# SAMV71_Xplained_Ultra_EDBG.net
KiCad netlist of a schematic drawn in Altium Designer
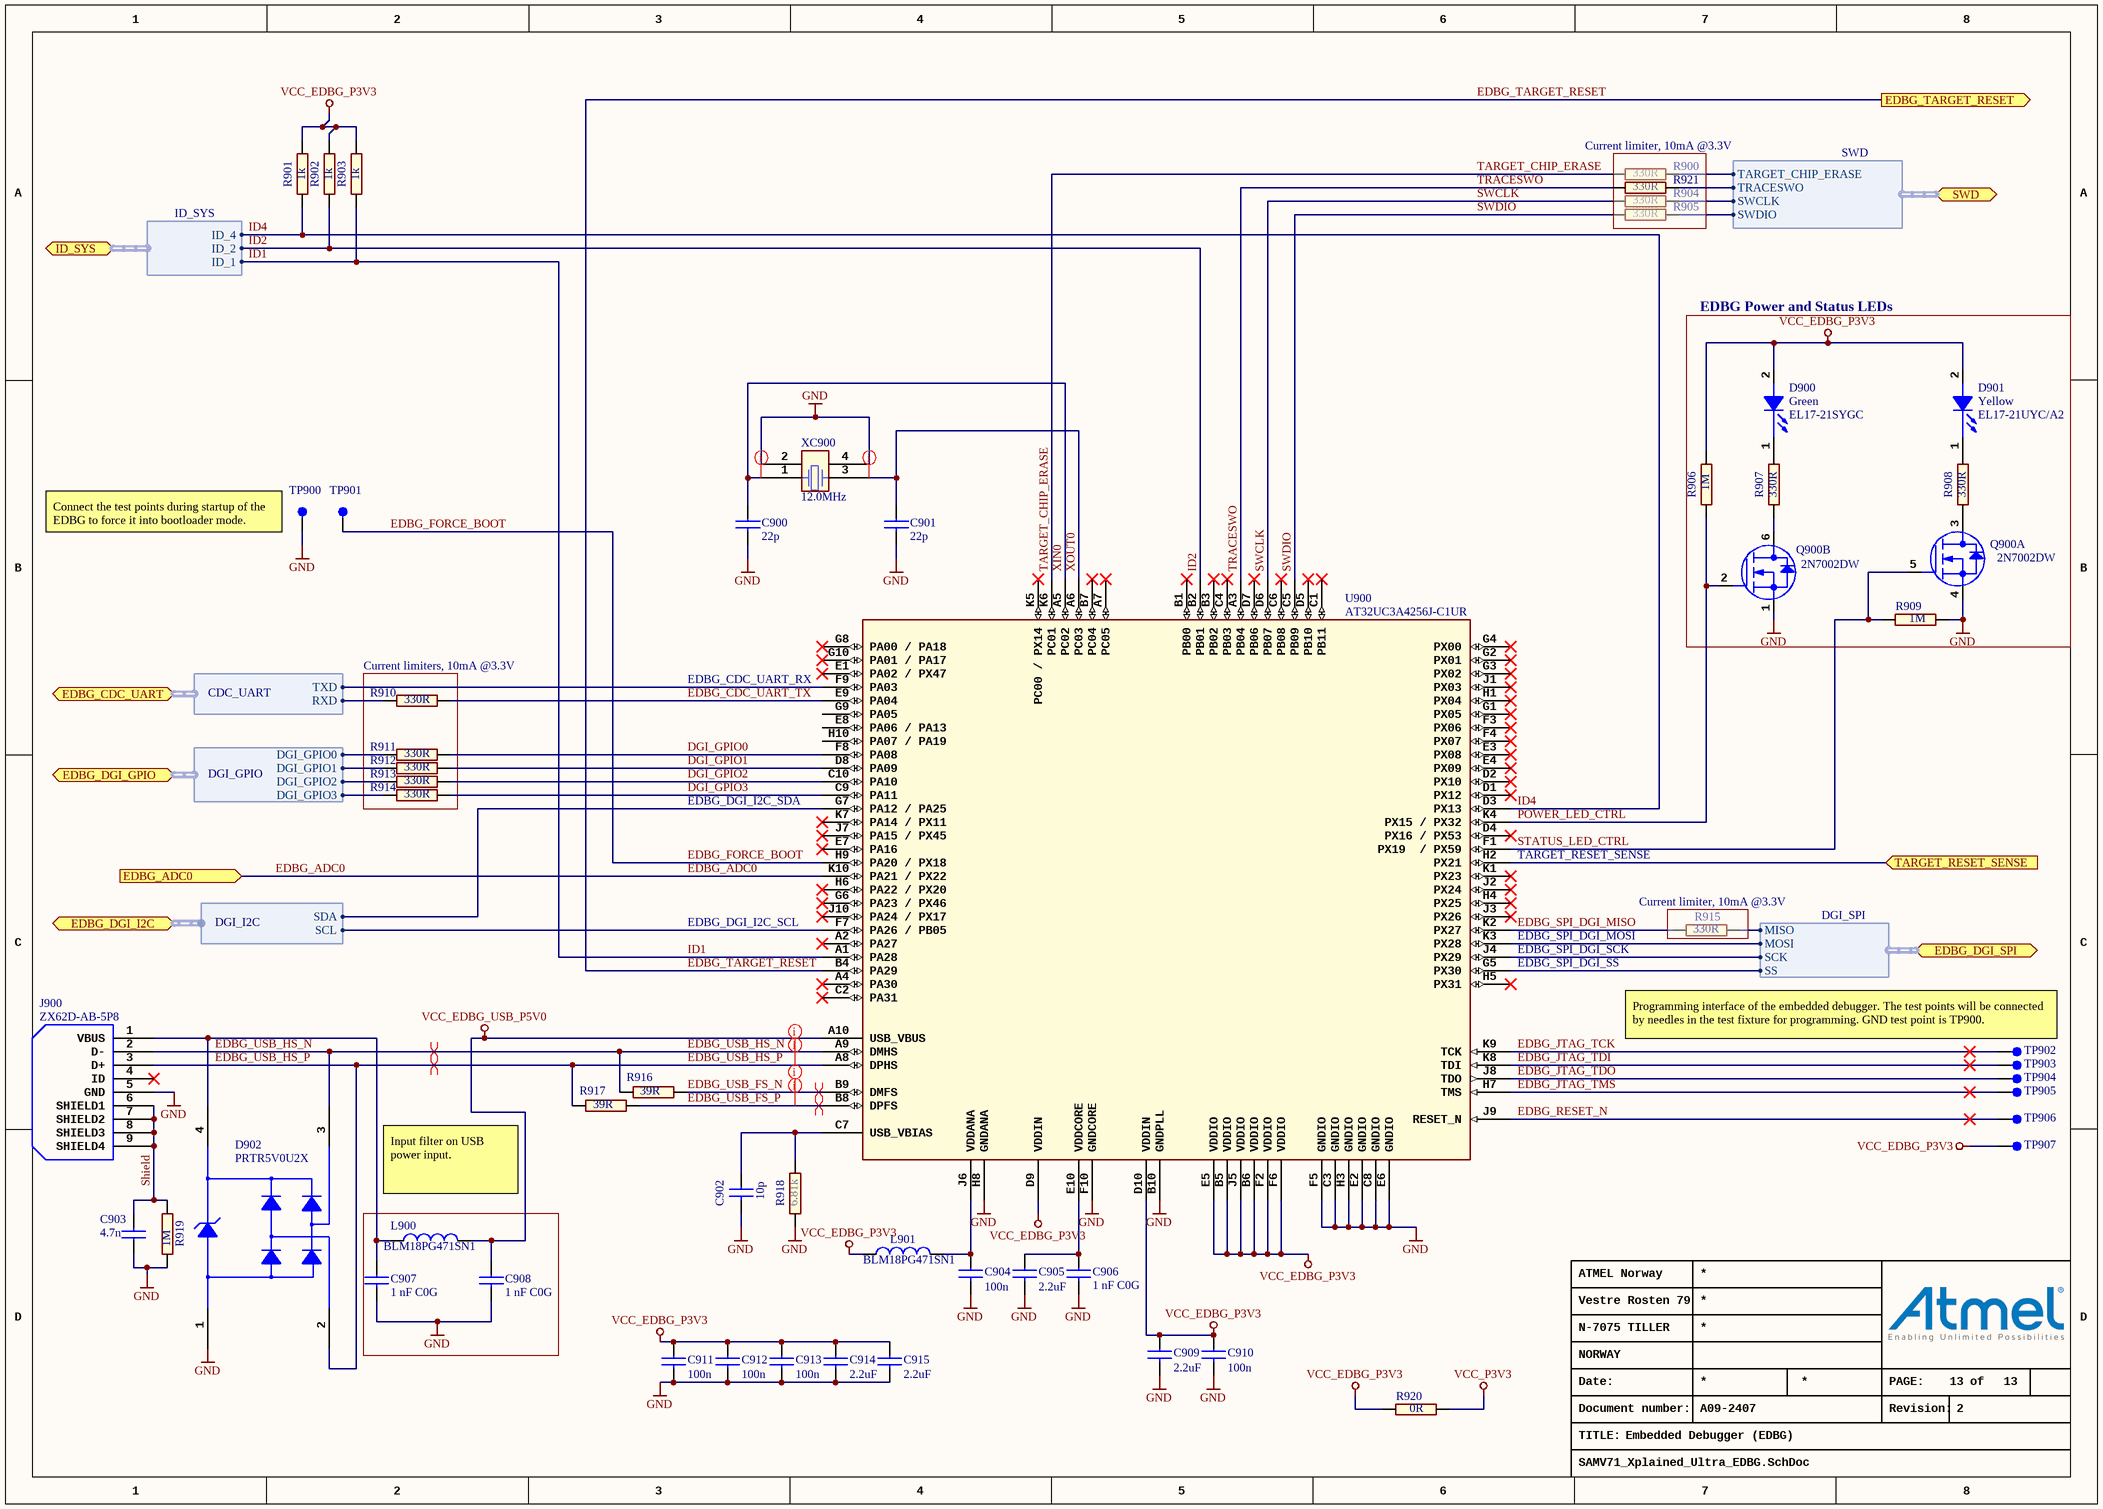
[diagram p0: SAMV71_Xplained_Ultra_EDBG.SchDoc]

(export (version "E")
  (design (tool "Eeschema 10.0.6"))
  (components
    (comp (ref "C900")
      (value "22p")
      (footprint "AP1-00053")
      (description "Ceramic capacitor, SMD 0402, NP0, 50V, +/-5%")
      (fields (field (name "TOLERANCE") "50V, +/-5%"))
      (libsource (lib "AltiumDbLib") (part "CAP-NONPOL"))
    )
    (comp (ref "C901")
      (value "22p")
      (footprint "AP1-00053")
      (description "Ceramic capacitor, SMD 0402, NP0, 50V, +/-5%")
      (fields (field (name "TOLERANCE") "50V, +/-5%"))
      (libsource (lib "AltiumDbLib") (part "CAP-NONPOL"))
    )
    (comp (ref "C902")
      (value "10p")
      (footprint "AP1-00053")
      (description "Ceramic capacitor, SMD 0402, NP0, 50V, +/-5%")
      (fields (field (name "TOLERANCE") "50V, +/-5%"))
      (libsource (lib "AltiumDbLib") (part "CAP-NONPOL"))
    )
    (comp (ref "C903")
      (value "4.7n")
      (footprint "AP1-00053")
      (description "Ceramic capacitor, SMD 0402, X7R, 25V, +/-10%")
      (fields (field (name "TOLERANCE") "25V, +/-10%") (field (name "Comment") "CAP-NONPOL"))
      (libsource (lib "AltiumDbLib") (part "CAP-NONPOL"))
    )
    (comp (ref "C904")
      (value "100n")
      (footprint "AP1-00053")
      (description "Ceramic capacitor, SMD 0402, X7R, 16V, +/-10%")
      (fields (field (name "TOLERANCE") "16V, +/-10%") (field (name "MANUFACTURER") "Kemet"))
      (libsource (lib "AltiumDbLib") (part "CAP-NONPOL"))
    )
    (comp (ref "C905")
      (value "2.2uF")
      (footprint "AP1-00053")
      (description "Ceramic capacitor, SMD 0402, X5R, 6.3V, +/-20%")
      (fields (field (name "TOLERANCE") "±20%") (field (name "MANUFACTURER") "Kemet"))
      (libsource (lib "AltiumDbLib") (part "CAP-NONPOL"))
    )
    (comp (ref "C906")
      (value "1 nF C0G")
      (footprint "AP1-00053")
      (description "Ceramic capacitor, SMD 0402, C0G, 50V, +/-5%")
      (fields (field (name "TOLERANCE") "5%") (field (name "MANUFACTURER") "Murata"))
      (libsource (lib "AltiumDbLib") (part "CAP-NONPOL"))
    )
    (comp (ref "C907")
      (value "1 nF C0G")
      (footprint "AP1-00053")
      (description "Ceramic capacitor, SMD 0402, C0G, 50V, +/-5%")
      (fields (field (name "TOLERANCE") "5%") (field (name "MANUFACTURER") "Murata"))
      (libsource (lib "AltiumDbLib") (part "CAP-NONPOL"))
    )
    (comp (ref "C908")
      (value "1 nF C0G")
      (footprint "AP1-00053")
      (description "Ceramic capacitor, SMD 0402, C0G, 50V, +/-5%")
      (fields (field (name "TOLERANCE") "5%") (field (name "MANUFACTURER") "Murata"))
      (libsource (lib "AltiumDbLib") (part "CAP-NONPOL"))
    )
    (comp (ref "C909")
      (value "2.2uF")
      (footprint "AP1-00053")
      (description "Ceramic capacitor, SMD 0402, X5R, 6.3V, +/-20%")
      (fields (field (name "TOLERANCE") "±20%") (field (name "MANUFACTURER") "Kemet"))
      (libsource (lib "AltiumDbLib") (part "CAP-NONPOL"))
    )
    (comp (ref "C910")
      (value "100n")
      (footprint "AP1-00053")
      (description "Ceramic capacitor, SMD 0402, X7R, 16V, +/-10%")
      (fields (field (name "TOLERANCE") "16V, +/-10%") (field (name "MANUFACTURER") "Kemet"))
      (libsource (lib "AltiumDbLib") (part "CAP-NONPOL"))
    )
    (comp (ref "C911")
      (value "100n")
      (footprint "AP1-00053")
      (description "Ceramic capacitor, SMD 0402, X7R, 16V, +/-10%")
      (fields (field (name "TOLERANCE") "16V, +/-10%") (field (name "MANUFACTURER") "Kemet"))
      (libsource (lib "AltiumDbLib") (part "CAP-NONPOL"))
    )
    (comp (ref "C912")
      (value "100n")
      (footprint "AP1-00053")
      (description "Ceramic capacitor, SMD 0402, X7R, 16V, +/-10%")
      (fields (field (name "TOLERANCE") "16V, +/-10%") (field (name "MANUFACTURER") "Kemet"))
      (libsource (lib "AltiumDbLib") (part "CAP-NONPOL"))
    )
    (comp (ref "C913")
      (value "100n")
      (footprint "AP1-00053")
      (description "Ceramic capacitor, SMD 0402, X7R, 16V, +/-10%")
      (fields (field (name "TOLERANCE") "16V, +/-10%") (field (name "MANUFACTURER") "Kemet"))
      (libsource (lib "AltiumDbLib") (part "CAP-NONPOL"))
    )
    (comp (ref "C914")
      (value "2.2uF")
      (footprint "AP1-00053")
      (description "Ceramic capacitor, SMD 0402, X5R, 6.3V, +/-20%")
      (fields (field (name "TOLERANCE") "±20%") (field (name "MANUFACTURER") "Kemet"))
      (libsource (lib "AltiumDbLib") (part "CAP-NONPOL"))
    )
    (comp (ref "C915")
      (value "2.2uF")
      (footprint "AP1-00053")
      (description "Ceramic capacitor, SMD 0402, X5R, 6.3V, +/-20%")
      (fields (field (name "TOLERANCE") "±20%") (field (name "MANUFACTURER") "Kemet"))
      (libsource (lib "AltiumDbLib") (part "CAP-NONPOL"))
    )
    (comp (ref "D900")
      (value "Green")
      (footprint "AP4-00013")
      (description "LED, Green, Wave length=575nm, SMD 0805, ±70°")
      (fields
        (field (name "ALTIUM_VALUE") "EL17-21SYGC")
        (field (name "MANUFACTURER") "Everlight")
        (field (name "MPN") "EL17-21SYGC")
      )
      (libsource (lib "AltiumDbLib") (part "LED_12"))
    )
    (comp (ref "D901")
      (value "Yellow")
      (footprint "AP4-00013")
      (description "LED, Yellow, Wave length=591nm, SMD 0805, ±70°")
      (fields
        (field (name "ALTIUM_VALUE") "EL17-21UYC/A2")
        (field (name "MANUFACTURER") "Everlight")
        (field (name "MPN") "17-21UYC/S530-A3/TR8")
      )
      (libsource (lib "AltiumDbLib") (part "LED_12"))
    )
    (comp (ref "D902")
      (value "PRTR5V0U2X")
      (footprint "AP4-00001")
      (description "Double rail-to-rail USB ESD protection diode")
      (fields (field (name "MANUFACTURER") "Philips"))
      (libsource (lib "AltiumDbLib") (part "PRTR5V0U2X"))
    )
    (comp (ref "J900")
      (value "ZX62D-AB-5P8")
      (footprint "AP8-00852")
      (description "Micro USB AB Connector, Standard SMT + DIP")
      (fields (field (name "Comment") "2,000 pieces per reel"))
      (libsource (lib "AltiumDbLib") (part "USB_AB"))
    )
    (comp (ref "L900")
      (value "BLM18PG471SN1")
      (footprint "AP3-00005")
      (description "SMD RF inductor 0603. Z=470Ohm (@100MHz), Max R(dc)=0.65Ohm, Max current=1A")
      (fields (field (name "TOLERANCE") "±25%") (field (name "MANUFACTURER") "Murata"))
      (libsource (lib "AltiumDbLib") (part "INDUCTOR"))
    )
    (comp (ref "L901")
      (value "BLM18PG471SN1")
      (footprint "AP3-00005")
      (description "SMD RF inductor 0603. Z=470Ohm (@100MHz), Max R(dc)=0.65Ohm, Max current=1A")
      (fields (field (name "TOLERANCE") "±25%") (field (name "MANUFACTURER") "Murata"))
      (libsource (lib "AltiumDbLib") (part "INDUCTOR"))
    )
    (comp (ref "Q900")
      (value "2N7002DW")
      (footprint "AP5-00001")
      (description "Dual N-Channel MOSFET, 60V, 115mA cont,RDS(ON) < 7.5 Ohm @50mA@5V, SOT-363")
      (fields
        (field (name "MANUFACTURER") "Fairchild")
        (field (name "Comment") "Same as 2N7002 but with two MOSFETs in one package")
      )
      (libsource (lib "AltiumDbLib") (part "MOSFET_DUAL_N_S2G2D1S1G1D2"))
    )
    (comp (ref "R900")
      (value "330R")
      (footprint "AP2-00000")
      (description "Thick film resistor, SMD 0402, 1/16W, 1%")
      (fields (field (name "TOLERANCE") "1 %") (field (name "Comment") "R2"))
      (libsource (lib "AltiumDbLib") (part "R2"))
    )
    (comp (ref "R901")
      (value "1k")
      (footprint "AP2-00000")
      (description "Thick film resistor, SMD 0402, 1/16W, 1%")
      (fields (field (name "TOLERANCE") "1 %") (field (name "Comment") "R2"))
      (libsource (lib "") (part "R2_2"))
    )
    (comp (ref "R902")
      (value "1k")
      (footprint "AP2-00000")
      (description "Thick film resistor, SMD 0402, 1/16W, 1%")
      (fields (field (name "TOLERANCE") "1 %") (field (name "Comment") "R2"))
      (libsource (lib "") (part "R2_2"))
    )
    (comp (ref "R903")
      (value "1k")
      (footprint "AP2-00000")
      (description "Thick film resistor, SMD 0402, 1/16W, 1%")
      (fields (field (name "TOLERANCE") "1 %") (field (name "Comment") "R2"))
      (libsource (lib "") (part "R2_2"))
    )
    (comp (ref "R904")
      (value "330R")
      (footprint "AP2-00000")
      (description "Thick film resistor, SMD 0402, 1/16W, 1%")
      (fields (field (name "TOLERANCE") "1 %") (field (name "Comment") "R2"))
      (libsource (lib "AltiumDbLib") (part "R2"))
    )
    (comp (ref "R905")
      (value "330R")
      (footprint "AP2-00000")
      (description "Thick film resistor, SMD 0402, 1/16W, 1%")
      (fields (field (name "TOLERANCE") "1 %") (field (name "Comment") "R2"))
      (libsource (lib "AltiumDbLib") (part "R2"))
    )
    (comp (ref "R906")
      (value "1M")
      (footprint "AP2-00000")
      (description "Thick film resistor, SMD 0402, 1/16W, 1%")
      (fields (field (name "TOLERANCE") "1 %") (field (name "MANUFACTURER") "KOA"))
      (libsource (lib "") (part "R2_2"))
    )
    (comp (ref "R907")
      (value "330R")
      (footprint "AP2-00000")
      (description "Thick film resistor, SMD 0402, 1/16W, 1%")
      (fields (field (name "TOLERANCE") "1 %") (field (name "Comment") "R2"))
      (libsource (lib "") (part "R2_2"))
    )
    (comp (ref "R908")
      (value "330R")
      (footprint "AP2-00000")
      (description "Thick film resistor, SMD 0402, 1/16W, 1%")
      (fields (field (name "TOLERANCE") "1 %") (field (name "Comment") "R2"))
      (libsource (lib "") (part "R2_2"))
    )
    (comp (ref "R909")
      (value "1M")
      (footprint "AP2-00000")
      (description "Thick film resistor, SMD 0402, 1/16W, 1%")
      (fields (field (name "TOLERANCE") "1 %") (field (name "MANUFACTURER") "KOA"))
      (libsource (lib "") (part "R2_4"))
    )
    (comp (ref "R910")
      (value "330R")
      (footprint "AP2-00000")
      (description "Thick film resistor, SMD 0402, 1/16W, 1%")
      (fields (field (name "TOLERANCE") "1 %") (field (name "Comment") "R2"))
      (libsource (lib "AltiumDbLib") (part "R2"))
    )
    (comp (ref "R911")
      (value "330R")
      (footprint "AP2-00000")
      (description "Thick film resistor, SMD 0402, 1/16W, 1%")
      (fields (field (name "TOLERANCE") "1 %") (field (name "Comment") "R2"))
      (libsource (lib "AltiumDbLib") (part "R2"))
    )
    (comp (ref "R912")
      (value "330R")
      (footprint "AP2-00000")
      (description "Thick film resistor, SMD 0402, 1/16W, 1%")
      (fields (field (name "TOLERANCE") "1 %") (field (name "Comment") "R2"))
      (libsource (lib "AltiumDbLib") (part "R2"))
    )
    (comp (ref "R913")
      (value "330R")
      (footprint "AP2-00000")
      (description "Thick film resistor, SMD 0402, 1/16W, 1%")
      (fields (field (name "TOLERANCE") "1 %") (field (name "Comment") "R2"))
      (libsource (lib "AltiumDbLib") (part "R2"))
    )
    (comp (ref "R914")
      (value "330R")
      (footprint "AP2-00000")
      (description "Thick film resistor, SMD 0402, 1/16W, 1%")
      (fields (field (name "TOLERANCE") "1 %") (field (name "Comment") "R2"))
      (libsource (lib "AltiumDbLib") (part "R2"))
    )
    (comp (ref "R915")
      (value "330R")
      (footprint "AP2-00000")
      (description "Thick film resistor, SMD 0402, 1/16W, 1%")
      (fields (field (name "TOLERANCE") "1 %") (field (name "Comment") "R2"))
      (libsource (lib "AltiumDbLib") (part "R2"))
    )
    (comp (ref "R916")
      (value "39R")
      (footprint "AP2-00011")
      (description "Thick film resistor, SMD 0402, 1/16W, 1%")
      (fields (field (name "TOLERANCE") "1 %") (field (name "Comment") "R2"))
      (libsource (lib "") (part "R2_1"))
    )
    (comp (ref "R917")
      (value "39R")
      (footprint "AP2-00011")
      (description "Thick film resistor, SMD 0402, 1/16W, 1%")
      (fields (field (name "TOLERANCE") "1 %") (field (name "Comment") "R2"))
      (libsource (lib "") (part "R2_1"))
    )
    (comp (ref "R918")
      (value "6.81k")
      (footprint "AP2-00011")
      (description "Thick film resistor, SMD 0402, 1/16W, 1%")
      (fields (field (name "TOLERANCE") "1%") (field (name "Comment") "R2"))
      (libsource (lib "") (part "R2_2"))
    )
    (comp (ref "R919")
      (value "1M")
      (footprint "AP2-00011")
      (description "Thick film resistor, SMD 0402, 1/16W, 1%")
      (fields (field (name "TOLERANCE") "1 %") (field (name "MANUFACTURER") "KOA"))
      (libsource (lib "") (part "R2_3"))
    )
    (comp (ref "R920")
      (value "0R")
      (footprint "AP2-00000")
      (description "Thick film resistor, SMD 0402, 1/16W, 1%")
      (fields (field (name "TOLERANCE") "1 %") (field (name "Comment") "R2"))
      (libsource (lib "AltiumDbLib") (part "R2"))
    )
    (comp (ref "R921")
      (value "330R")
      (footprint "AP2-00000")
      (description "Thick film resistor, SMD 0402, 1/16W, 1%")
      (fields (field (name "TOLERANCE") "1 %") (field (name "Comment") "R2"))
      (libsource (lib "AltiumDbLib") (part "R2"))
    )
    (comp (ref "TP900")
      (value "TESTPOINT")
      (footprint "AP8-00010")
      (description "Single SMD testpad")
      (libsource (lib "AltiumDbLib") (part "TESTPOINT"))
    )
    (comp (ref "TP901")
      (value "TESTPOINT")
      (footprint "AP8-00010")
      (description "Single SMD testpad")
      (libsource (lib "AltiumDbLib") (part "TESTPOINT"))
    )
    (comp (ref "TP902")
      (value "TESTPOINT")
      (footprint "AP8-00010")
      (description "Single SMD testpad")
      (libsource (lib "AltiumDbLib") (part "TESTPOINT"))
    )
    (comp (ref "TP903")
      (value "TESTPOINT")
      (footprint "AP8-00010")
      (description "Single SMD testpad")
      (libsource (lib "AltiumDbLib") (part "TESTPOINT"))
    )
    (comp (ref "TP904")
      (value "TESTPOINT")
      (footprint "AP8-00010")
      (description "Single SMD testpad")
      (libsource (lib "AltiumDbLib") (part "TESTPOINT"))
    )
    (comp (ref "TP905")
      (value "TESTPOINT")
      (footprint "AP8-00010")
      (description "Single SMD testpad")
      (libsource (lib "AltiumDbLib") (part "TESTPOINT"))
    )
    (comp (ref "TP906")
      (value "TESTPOINT")
      (footprint "AP8-00010")
      (description "Single SMD testpad")
      (libsource (lib "AltiumDbLib") (part "TESTPOINT"))
    )
    (comp (ref "TP907")
      (value "TESTPOINT")
      (footprint "AP8-00010")
      (description "Single SMD testpad")
      (libsource (lib "AltiumDbLib") (part "TESTPOINT"))
    )
    (comp (ref "U900")
      (value "AT32UC3A4256J-C1UR")
      (footprint "AP6-00206")
      (description "AVR 32-bit RISC MCU")
      (fields (field (name "MANUFACTURER") "ATMEL") (field (name "Comment") "100 ball VFBGA"))
      (libsource (lib "AltiumDbLib") (part "AT32UC3A4_VFBGA"))
    )
    (comp (ref "XC900")
      (value "12.0MHz")
      (footprint "AP7-00039")
      (description "Fox FQ5032B 12.0MHz SMD crystal 738B-12")
      (fields (field (name "TOLERANCE") "30PPM") (field (name "MANUFACTURER") "Fox  Electronics"))
      (libsource (lib "AltiumDbLib") (part "CRYSTAL1324"))
    )
  )
  (nets
    (net (code "7") (name "/DGI_GPIO0") (class "Default")
      (node (ref "R911") (pin "2") (pinfunction "2_2") (pintype "passive"))
      (node (ref "U900") (pin "F8") (pinfunction "PA08_F8") (pintype "bidirectional"))
    )
    (net (code "8") (name "/DGI_GPIO1") (class "Default")
      (node (ref "R912") (pin "2") (pinfunction "2_2") (pintype "passive"))
      (node (ref "U900") (pin "D8") (pinfunction "PA09_D8") (pintype "bidirectional"))
    )
    (net (code "9") (name "/DGI_GPIO2") (class "Default")
      (node (ref "R913") (pin "2") (pinfunction "2_2") (pintype "passive"))
      (node (ref "U900") (pin "C10") (pinfunction "PA10_C10") (pintype "bidirectional"))
    )
    (net (code "10") (name "/DGI_GPIO3") (class "Default")
      (node (ref "R914") (pin "2") (pinfunction "2_2") (pintype "passive"))
      (node (ref "U900") (pin "C9") (pinfunction "PA11_C9") (pintype "bidirectional"))
    )
    (net (code "11") (name "/EDBG_ADC0") (class "Default")
      (node (ref "U900") (pin "K10") (pinfunction "PA21_/_PX22_K10") (pintype "bidirectional"))
    )
    (net (code "12") (name "/EDBG_CDC_UART_TX") (class "Default")
      (node (ref "R910") (pin "2") (pinfunction "2_2") (pintype "passive"))
      (node (ref "U900") (pin "E9") (pinfunction "PA04_E9") (pintype "bidirectional"))
    )
    (net (code "13") (name "/EDBG_FORCE_BOOT") (class "Default")
      (node (ref "TP901") (pin "1") (pinfunction "1_1") (pintype "passive"))
      (node (ref "U900") (pin "H9") (pinfunction "PA20_/_PX18_H9") (pintype "bidirectional"))
    )
    (net (code "14") (name "/EDBG_JTAG_TCK") (class "Default")
      (node (ref "TP902") (pin "1") (pinfunction "1_1") (pintype "passive"))
      (node (ref "U900") (pin "K9") (pinfunction "TCK_K9") (pintype "input"))
    )
    (net (code "15") (name "/EDBG_JTAG_TDI") (class "Default")
      (node (ref "TP903") (pin "1") (pinfunction "1_1") (pintype "passive"))
      (node (ref "U900") (pin "K8") (pinfunction "TDI_K8") (pintype "input"))
    )
    (net (code "16") (name "/EDBG_JTAG_TDO") (class "Default")
      (node (ref "TP904") (pin "1") (pinfunction "1_1") (pintype "passive"))
      (node (ref "U900") (pin "J8") (pinfunction "TDO_J8") (pintype "output"))
    )
    (net (code "17") (name "/EDBG_JTAG_TMS") (class "Default")
      (node (ref "TP905") (pin "1") (pinfunction "1_1") (pintype "passive"))
      (node (ref "U900") (pin "H7") (pinfunction "TMS_H7") (pintype "input"))
    )
    (net (code "18") (name "/EDBG_RESET_N") (class "Default")
      (node (ref "TP906") (pin "1") (pinfunction "1_1") (pintype "passive"))
      (node (ref "U900") (pin "J9") (pinfunction "RESET_N_J9") (pintype "input"))
    )
    (net (code "19") (name "/EDBG_SPI_DGI_MISO") (class "Default")
      (node (ref "R915") (pin "1") (pinfunction "1_1") (pintype "passive"))
      (node (ref "U900") (pin "K2") (pinfunction "PX27_K2") (pintype "bidirectional"))
    )
    (net (code "20") (name "/EDBG_TARGET_RESET") (class "Default")
      (node (ref "U900") (pin "B4") (pinfunction "PA29_B4") (pintype "bidirectional"))
    )
    (net (code "21") (name "/EDBG_USB_FS_N") (class "Default")
      (node (ref "R916") (pin "2") (pinfunction "2_2") (pintype "passive"))
      (node (ref "U900") (pin "B9") (pinfunction "DMFS_B9") (pintype "bidirectional"))
    )
    (net (code "22") (name "/EDBG_USB_FS_P") (class "Default")
      (node (ref "R917") (pin "2") (pinfunction "2_2") (pintype "passive"))
      (node (ref "U900") (pin "B8") (pinfunction "DPFS_B8") (pintype "bidirectional"))
    )
    (net (code "23") (name "/EDBG_USB_HS_N") (class "Default")
      (node (ref "D902") (pin "3") (pinfunction "I/O_2_3") (pintype "passive"))
      (node (ref "J900") (pin "2") (pinfunction "D-_2") (pintype "passive"))
      (node (ref "R916") (pin "1") (pinfunction "1_1") (pintype "passive"))
      (node (ref "U900") (pin "A9") (pinfunction "DMHS_A9") (pintype "bidirectional"))
    )
    (net (code "24") (name "/EDBG_USB_HS_P") (class "Default")
      (node (ref "D902") (pin "2") (pinfunction "I/O_1_2") (pintype "passive"))
      (node (ref "J900") (pin "3") (pinfunction "D+_3") (pintype "passive"))
      (node (ref "R917") (pin "1") (pinfunction "1_1") (pintype "passive"))
      (node (ref "U900") (pin "A8") (pinfunction "DPHS_A8") (pintype "bidirectional"))
    )
    (net (code "25") (name "/ID1") (class "Default")
      (node (ref "R903") (pin "1") (pinfunction "1_1") (pintype "passive"))
      (node (ref "U900") (pin "A1") (pinfunction "PA28_A1") (pintype "bidirectional"))
    )
    (net (code "26") (name "/ID2") (class "Default")
      (node (ref "R902") (pin "1") (pinfunction "1_1") (pintype "passive"))
      (node (ref "U900") (pin "B2") (pinfunction "PB01_B2") (pintype "bidirectional"))
    )
    (net (code "27") (name "/ID4") (class "Default")
      (node (ref "R901") (pin "1") (pinfunction "1_1") (pintype "passive"))
      (node (ref "U900") (pin "D3") (pinfunction "PX13_D3") (pintype "bidirectional"))
    )
    (net (code "28") (name "/MISO") (class "Default")
      (node (ref "R915") (pin "2") (pinfunction "2_2") (pintype "passive"))
    )
    (net (code "29") (name "/MOSI") (class "Default")
      (node (ref "U900") (pin "K3") (pinfunction "PX28_K3") (pintype "bidirectional"))
    )
    (net (code "30") (name "/POWER_LED_CTRL") (class "Default")
      (node (ref "Q900") (pin "2") (pinfunction "G2_2") (pintype "passive"))
      (node (ref "R906") (pin "1") (pinfunction "1_1") (pintype "passive"))
      (node (ref "U900") (pin "K4") (pinfunction "PX15_/_PX32_K4") (pintype "bidirectional"))
    )
    (net (code "31") (name "/RXD") (class "Default")
      (node (ref "R910") (pin "1") (pinfunction "1_1") (pintype "passive"))
    )
    (net (code "32") (name "/SCK") (class "Default")
      (node (ref "U900") (pin "J4") (pinfunction "PX29_J4") (pintype "bidirectional"))
    )
    (net (code "33") (name "/SCL") (class "Default")
      (node (ref "U900") (pin "F7") (pinfunction "PA26_/_PB05_F7") (pintype "bidirectional"))
    )
    (net (code "34") (name "/SDA") (class "Default")
      (node (ref "U900") (pin "G7") (pinfunction "PA12_/_PA25_G7") (pintype "bidirectional"))
    )
    (net (code "35") (name "/SS") (class "Default")
      (node (ref "U900") (pin "G5") (pinfunction "PX30_G5") (pintype "bidirectional"))
    )
    (net (code "36") (name "/STATUS_LED_CTRL") (class "Default")
      (node (ref "Q900") (pin "5") (pinfunction "G1_5") (pintype "passive"))
      (node (ref "R909") (pin "2") (pinfunction "2_2") (pintype "passive"))
      (node (ref "U900") (pin "F1") (pinfunction "PX19__/_PX59_F1") (pintype "bidirectional"))
    )
    (net (code "37") (name "/SWCLK") (class "Default")
      (node (ref "R904") (pin "1") (pinfunction "1_1") (pintype "passive"))
      (node (ref "U900") (pin "D6") (pinfunction "PB07_D6") (pintype "bidirectional"))
    )
    (net (code "38") (name "/SWDIO") (class "Default")
      (node (ref "R905") (pin "1") (pinfunction "1_1") (pintype "passive"))
      (node (ref "U900") (pin "C5") (pinfunction "PB09_C5") (pintype "bidirectional"))
    )
    (net (code "39") (name "/Shield") (class "Default")
      (node (ref "C903") (pin "2") (pinfunction "2_2") (pintype "passive"))
      (node (ref "J900") (pin "6") (pinfunction "SHIELD1_6") (pintype "passive"))
      (node (ref "J900") (pin "7") (pinfunction "SHIELD2_7") (pintype "passive"))
      (node (ref "J900") (pin "8") (pinfunction "SHIELD3_8") (pintype "passive"))
      (node (ref "J900") (pin "9") (pinfunction "SHIELD4_9") (pintype "passive"))
      (node (ref "R919") (pin "2") (pinfunction "2_2") (pintype "passive"))
    )
    (net (code "40") (name "/TARGET_CHIP_ERASE") (class "Default")
      (node (ref "R900") (pin "1") (pinfunction "1_1") (pintype "passive"))
      (node (ref "U900") (pin "K6") (pinfunction "PC01_K6") (pintype "bidirectional"))
    )
    (net (code "41") (name "/TARGET_RESET_SENSE") (class "Default")
      (node (ref "U900") (pin "H2") (pinfunction "PX21_H2") (pintype "bidirectional"))
    )
    (net (code "42") (name "/TRACESWO") (class "Default")
      (node (ref "R921") (pin "1") (pinfunction "1_1") (pintype "passive"))
      (node (ref "U900") (pin "A3") (pinfunction "PB04_A3") (pintype "bidirectional"))
    )
    (net (code "43") (name "/TXD") (class "Default")
      (node (ref "U900") (pin "F9") (pinfunction "PA03_F9") (pintype "bidirectional"))
    )
    (net (code "44") (name "/XIN0") (class "Default")
      (node (ref "C900") (pin "1") (pinfunction "1_1") (pintype "passive"))
      (node (ref "U900") (pin "A5") (pinfunction "PC02_A5") (pintype "bidirectional"))
      (node (ref "XC900") (pin "1") (pinfunction "1_1") (pintype "passive"))
    )
    (net (code "45") (name "/XOUT0") (class "Default")
      (node (ref "C901") (pin "1") (pinfunction "1_1") (pintype "passive"))
      (node (ref "U900") (pin "A6") (pinfunction "PC03_A6") (pintype "bidirectional"))
      (node (ref "XC900") (pin "3") (pinfunction "3_3") (pintype "passive"))
    )
    (net (code "52") (name "GND") (class "Default")
      (node (ref "C900") (pin "2") (pinfunction "2_2") (pintype "passive"))
      (node (ref "C901") (pin "2") (pinfunction "2_2") (pintype "passive"))
      (node (ref "C902") (pin "2") (pinfunction "2_2") (pintype "passive"))
      (node (ref "C903") (pin "1") (pinfunction "1_1") (pintype "passive"))
      (node (ref "C904") (pin "2") (pinfunction "2_2") (pintype "passive"))
      (node (ref "C905") (pin "2") (pinfunction "2_2") (pintype "passive"))
      (node (ref "C906") (pin "2") (pinfunction "2_2") (pintype "passive"))
      (node (ref "C907") (pin "2") (pinfunction "2_2") (pintype "passive"))
      (node (ref "C908") (pin "2") (pinfunction "2_2") (pintype "passive"))
      (node (ref "C909") (pin "2") (pinfunction "2_2") (pintype "passive"))
      (node (ref "C910") (pin "2") (pinfunction "2_2") (pintype "passive"))
      (node (ref "C911") (pin "2") (pinfunction "2_2") (pintype "passive"))
      (node (ref "C912") (pin "2") (pinfunction "2_2") (pintype "passive"))
      (node (ref "C913") (pin "2") (pinfunction "2_2") (pintype "passive"))
      (node (ref "C914") (pin "2") (pinfunction "2_2") (pintype "passive"))
      (node (ref "C915") (pin "2") (pinfunction "2_2") (pintype "passive"))
      (node (ref "D902") (pin "1") (pinfunction "GND_1") (pintype "passive"))
      (node (ref "J900") (pin "5") (pinfunction "GND_5") (pintype "passive"))
      (node (ref "Q900") (pin "1") (pinfunction "S2_1") (pintype "passive"))
      (node (ref "Q900") (pin "4") (pinfunction "S1_4") (pintype "passive"))
      (node (ref "R909") (pin "1") (pinfunction "1_1") (pintype "passive"))
      (node (ref "R918") (pin "1") (pinfunction "1_1") (pintype "passive"))
      (node (ref "R919") (pin "1") (pinfunction "1_1") (pintype "passive"))
      (node (ref "TP900") (pin "1") (pinfunction "1_1") (pintype "passive"))
      (node (ref "U900") (pin "B10") (pinfunction "GNDPLL_B10") (pintype "power_in"))
      (node (ref "U900") (pin "C3") (pinfunction "GNDIO_C3") (pintype "power_in"))
      (node (ref "U900") (pin "C8") (pinfunction "GNDIO_C8") (pintype "power_in"))
      (node (ref "U900") (pin "E2") (pinfunction "GNDIO_E2") (pintype "power_in"))
      (node (ref "U900") (pin "E6") (pinfunction "GNDIO_E6") (pintype "power_in"))
      (node (ref "U900") (pin "F10") (pinfunction "GNDCORE_F10") (pintype "power_in"))
      (node (ref "U900") (pin "F5") (pinfunction "GNDIO_F5") (pintype "power_in"))
      (node (ref "U900") (pin "H3") (pinfunction "GNDIO_H3") (pintype "power_in"))
      (node (ref "U900") (pin "H8") (pinfunction "GNDANA_H8") (pintype "power_in"))
      (node (ref "XC900") (pin "2") (pinfunction "2_2") (pintype "passive"))
      (node (ref "XC900") (pin "4") (pinfunction "4_4") (pintype "passive"))
    )
    (net (code "53") (name "Net-(D900-CATHODE)") (class "Default")
      (node (ref "D900") (pin "1") (pinfunction "CATHODE_1") (pintype "passive"))
      (node (ref "R907") (pin "2") (pinfunction "2_2") (pintype "passive"))
    )
    (net (code "54") (name "Net-(D901-CATHODE)") (class "Default")
      (node (ref "D901") (pin "1") (pinfunction "CATHODE_1") (pintype "passive"))
      (node (ref "R908") (pin "2") (pinfunction "2_2") (pintype "passive"))
    )
    (net (code "55") (name "Net-(D902-VCC)") (class "Default")
      (node (ref "C907") (pin "1") (pinfunction "1_1") (pintype "passive"))
      (node (ref "D902") (pin "4") (pinfunction "VCC_4") (pintype "passive"))
      (node (ref "J900") (pin "1") (pinfunction "VBUS_1") (pintype "passive"))
      (node (ref "L900") (pin "1") (pinfunction "1_1") (pintype "passive"))
    )
    (net (code "56") (name "Net-(Q900A-D1)") (class "Default")
      (node (ref "Q900") (pin "3") (pinfunction "D1_3") (pintype "passive"))
      (node (ref "R908") (pin "1") (pinfunction "1_1") (pintype "passive"))
    )
    (net (code "57") (name "Net-(Q900B-D2)") (class "Default")
      (node (ref "Q900") (pin "6") (pinfunction "D2_6") (pintype "passive"))
      (node (ref "R907") (pin "1") (pinfunction "1_1") (pintype "passive"))
    )
    (net (code "58") (name "Net-(U900-USB_VBIAS)") (class "Default")
      (node (ref "C902") (pin "1") (pinfunction "1_1") (pintype "passive"))
      (node (ref "R918") (pin "2") (pinfunction "2_2") (pintype "passive"))
      (node (ref "U900") (pin "C7") (pinfunction "USB_VBIAS_C7") (pintype "power_in"))
    )
    (net (code "59") (name "Net-(U900-VDDANA)") (class "Default")
      (node (ref "C904") (pin "1") (pinfunction "1_1") (pintype "passive"))
      (node (ref "L901") (pin "2") (pinfunction "2_2") (pintype "passive"))
      (node (ref "U900") (pin "J6") (pinfunction "VDDANA_J6") (pintype "power_in"))
    )
    (net (code "60") (name "Net-(U900-VDDCORE)") (class "Default")
      (node (ref "C905") (pin "1") (pinfunction "1_1") (pintype "passive"))
      (node (ref "C906") (pin "1") (pinfunction "1_1") (pintype "passive"))
      (node (ref "U900") (pin "E10") (pinfunction "VDDCORE_E10") (pintype "power_in"))
    )
    (net (code "61") (name "VCC_EDBG_P3V3") (class "Default")
      (node (ref "C909") (pin "1") (pinfunction "1_1") (pintype "passive"))
      (node (ref "C910") (pin "1") (pinfunction "1_1") (pintype "passive"))
      (node (ref "C911") (pin "1") (pinfunction "1_1") (pintype "passive"))
      (node (ref "C912") (pin "1") (pinfunction "1_1") (pintype "passive"))
      (node (ref "C913") (pin "1") (pinfunction "1_1") (pintype "passive"))
      (node (ref "C914") (pin "1") (pinfunction "1_1") (pintype "passive"))
      (node (ref "C915") (pin "1") (pinfunction "1_1") (pintype "passive"))
      (node (ref "D900") (pin "2") (pinfunction "ANODE_2") (pintype "passive"))
      (node (ref "D901") (pin "2") (pinfunction "ANODE_2") (pintype "passive"))
      (node (ref "L901") (pin "1") (pinfunction "1_1") (pintype "passive"))
      (node (ref "R901") (pin "2") (pinfunction "2_2") (pintype "passive"))
      (node (ref "R902") (pin "2") (pinfunction "2_2") (pintype "passive"))
      (node (ref "R903") (pin "2") (pinfunction "2_2") (pintype "passive"))
      (node (ref "R906") (pin "2") (pinfunction "2_2") (pintype "passive"))
      (node (ref "R920") (pin "1") (pinfunction "1_1") (pintype "passive"))
      (node (ref "TP907") (pin "1") (pinfunction "1_1") (pintype "passive"))
      (node (ref "U900") (pin "B5") (pinfunction "VDDIO_B5") (pintype "power_in"))
      (node (ref "U900") (pin "B6") (pinfunction "VDDIO_B6") (pintype "power_in"))
      (node (ref "U900") (pin "D10") (pinfunction "VDDIN_D10") (pintype "power_in"))
      (node (ref "U900") (pin "D9") (pinfunction "VDDIN_D9") (pintype "power_in"))
      (node (ref "U900") (pin "E5") (pinfunction "VDDIO_E5") (pintype "power_in"))
      (node (ref "U900") (pin "F2") (pinfunction "VDDIO_F2") (pintype "power_in"))
      (node (ref "U900") (pin "F6") (pinfunction "VDDIO_F6") (pintype "power_in"))
      (node (ref "U900") (pin "J5") (pinfunction "VDDIO_J5") (pintype "power_in"))
    )
    (net (code "62") (name "VCC_EDBG_USB_P5V0") (class "Default")
      (node (ref "C908") (pin "1") (pinfunction "1_1") (pintype "passive"))
      (node (ref "L900") (pin "2") (pinfunction "2_2") (pintype "passive"))
      (node (ref "U900") (pin "A10") (pinfunction "USB_VBUS_A10") (pintype "power_in"))
    )
    (net (code "63") (name "VCC_P3V3") (class "Default")
      (node (ref "R920") (pin "2") (pinfunction "2_2") (pintype "passive"))
    )
    (net (code "64") (name "unconnected-(J900-ID-Pad4)") (class "Default")
      (node (ref "J900") (pin "4") (pinfunction "ID_4") (pintype "passive+no_connect"))
    )
    (net (code "65") (name "unconnected-(R900-Pad2)") (class "Default")
      (node (ref "R900") (pin "2") (pinfunction "2_2") (pintype "passive"))
    )
    (net (code "66") (name "unconnected-(R904-Pad2)") (class "Default")
      (node (ref "R904") (pin "2") (pinfunction "2_2") (pintype "passive"))
    )
    (net (code "67") (name "unconnected-(R905-Pad2)") (class "Default")
      (node (ref "R905") (pin "2") (pinfunction "2_2") (pintype "passive"))
    )
    (net (code "68") (name "unconnected-(R911-Pad1)") (class "Default")
      (node (ref "R911") (pin "1") (pinfunction "1_1") (pintype "passive"))
    )
    (net (code "69") (name "unconnected-(R912-Pad1)") (class "Default")
      (node (ref "R912") (pin "1") (pinfunction "1_1") (pintype "passive"))
    )
    (net (code "70") (name "unconnected-(R913-Pad1)") (class "Default")
      (node (ref "R913") (pin "1") (pinfunction "1_1") (pintype "passive"))
    )
    (net (code "71") (name "unconnected-(R914-Pad1)") (class "Default")
      (node (ref "R914") (pin "1") (pinfunction "1_1") (pintype "passive"))
    )
    (net (code "72") (name "unconnected-(R921-Pad2)") (class "Default")
      (node (ref "R921") (pin "2") (pinfunction "2_2") (pintype "passive"))
    )
    (net (code "73") (name "unconnected-(U900-PA00_{slash}_PA18-PadG8)") (class "Default")
      (node (ref "U900") (pin "G8") (pinfunction "PA00_/_PA18_G8") (pintype "bidirectional+no_connect"))
    )
    (net (code "74") (name "unconnected-(U900-PA01_{slash}_PA17-PadG10)") (class "Default")
      (node (ref "U900") (pin "G10") (pinfunction "PA01_/_PA17_G10") (pintype "bidirectional+no_connect"))
    )
    (net (code "75") (name "unconnected-(U900-PA02_{slash}_PX47-PadE1)") (class "Default")
      (node (ref "U900") (pin "E1") (pinfunction "PA02_/_PX47_E1") (pintype "bidirectional+no_connect"))
    )
    (net (code "76") (name "unconnected-(U900-PA05-PadG9)") (class "Default")
      (node (ref "U900") (pin "G9") (pinfunction "PA05_G9") (pintype "bidirectional"))
    )
    (net (code "77") (name "unconnected-(U900-PA06_{slash}_PA13-PadE8)") (class "Default")
      (node (ref "U900") (pin "E8") (pinfunction "PA06_/_PA13_E8") (pintype "bidirectional"))
    )
    (net (code "78") (name "unconnected-(U900-PA07_{slash}_PA19-PadH10)") (class "Default")
      (node (ref "U900") (pin "H10") (pinfunction "PA07_/_PA19_H10") (pintype "bidirectional"))
    )
    (net (code "79") (name "unconnected-(U900-PA14_{slash}_PX11-PadK7)") (class "Default")
      (node (ref "U900") (pin "K7") (pinfunction "PA14_/_PX11_K7") (pintype "bidirectional+no_connect"))
    )
    (net (code "80") (name "unconnected-(U900-PA15_{slash}_PX45-PadJ7)") (class "Default")
      (node (ref "U900") (pin "J7") (pinfunction "PA15_/_PX45_J7") (pintype "bidirectional+no_connect"))
    )
    (net (code "81") (name "unconnected-(U900-PA16-PadE7)") (class "Default")
      (node (ref "U900") (pin "E7") (pinfunction "PA16_E7") (pintype "bidirectional+no_connect"))
    )
    (net (code "82") (name "unconnected-(U900-PA22_{slash}_PX20-PadH6)") (class "Default")
      (node (ref "U900") (pin "H6") (pinfunction "PA22_/_PX20_H6") (pintype "bidirectional+no_connect"))
    )
    (net (code "83") (name "unconnected-(U900-PA23_{slash}_PX46-PadG6)") (class "Default")
      (node (ref "U900") (pin "G6") (pinfunction "PA23_/_PX46_G6") (pintype "bidirectional+no_connect"))
    )
    (net (code "84") (name "unconnected-(U900-PA24_{slash}_PX17-PadJ10)") (class "Default")
      (node (ref "U900") (pin "J10") (pinfunction "PA24_/_PX17_J10") (pintype "bidirectional+no_connect"))
    )
    (net (code "85") (name "unconnected-(U900-PA27-PadA2)") (class "Default")
      (node (ref "U900") (pin "A2") (pinfunction "PA27_A2") (pintype "bidirectional+no_connect"))
    )
    (net (code "86") (name "unconnected-(U900-PA30-PadA4)") (class "Default")
      (node (ref "U900") (pin "A4") (pinfunction "PA30_A4") (pintype "bidirectional+no_connect"))
    )
    (net (code "87") (name "unconnected-(U900-PA31-PadC2)") (class "Default")
      (node (ref "U900") (pin "C2") (pinfunction "PA31_C2") (pintype "bidirectional+no_connect"))
    )
    (net (code "88") (name "unconnected-(U900-PB00-PadB1)") (class "Default")
      (node (ref "U900") (pin "B1") (pinfunction "PB00_B1") (pintype "bidirectional+no_connect"))
    )
    (net (code "89") (name "unconnected-(U900-PB02-PadB3)") (class "Default")
      (node (ref "U900") (pin "B3") (pinfunction "PB02_B3") (pintype "bidirectional+no_connect"))
    )
    (net (code "90") (name "unconnected-(U900-PB03-PadC4)") (class "Default")
      (node (ref "U900") (pin "C4") (pinfunction "PB03_C4") (pintype "bidirectional+no_connect"))
    )
    (net (code "91") (name "unconnected-(U900-PB06-PadD7)") (class "Default")
      (node (ref "U900") (pin "D7") (pinfunction "PB06_D7") (pintype "bidirectional+no_connect"))
    )
    (net (code "92") (name "unconnected-(U900-PB08-PadC6)") (class "Default")
      (node (ref "U900") (pin "C6") (pinfunction "PB08_C6") (pintype "bidirectional+no_connect"))
    )
    (net (code "93") (name "unconnected-(U900-PB10-PadD5)") (class "Default")
      (node (ref "U900") (pin "D5") (pinfunction "PB10_D5") (pintype "bidirectional+no_connect"))
    )
    (net (code "94") (name "unconnected-(U900-PB11-PadC1)") (class "Default")
      (node (ref "U900") (pin "C1") (pinfunction "PB11_C1") (pintype "bidirectional+no_connect"))
    )
    (net (code "95") (name "unconnected-(U900-PC00_{slash}_PX14-PadK5)") (class "Default")
      (node (ref "U900") (pin "K5") (pinfunction "PC00_/_PX14_K5") (pintype "bidirectional+no_connect"))
    )
    (net (code "96") (name "unconnected-(U900-PC04-PadB7)") (class "Default")
      (node (ref "U900") (pin "B7") (pinfunction "PC04_B7") (pintype "bidirectional+no_connect"))
    )
    (net (code "97") (name "unconnected-(U900-PC05-PadA7)") (class "Default")
      (node (ref "U900") (pin "A7") (pinfunction "PC05_A7") (pintype "bidirectional+no_connect"))
    )
    (net (code "98") (name "unconnected-(U900-PX00-PadG4)") (class "Default")
      (node (ref "U900") (pin "G4") (pinfunction "PX00_G4") (pintype "bidirectional+no_connect"))
    )
    (net (code "99") (name "unconnected-(U900-PX01-PadG2)") (class "Default")
      (node (ref "U900") (pin "G2") (pinfunction "PX01_G2") (pintype "bidirectional+no_connect"))
    )
    (net (code "100") (name "unconnected-(U900-PX02-PadG3)") (class "Default")
      (node (ref "U900") (pin "G3") (pinfunction "PX02_G3") (pintype "bidirectional+no_connect"))
    )
    (net (code "101") (name "unconnected-(U900-PX03-PadJ1)") (class "Default")
      (node (ref "U900") (pin "J1") (pinfunction "PX03_J1") (pintype "bidirectional+no_connect"))
    )
    (net (code "102") (name "unconnected-(U900-PX04-PadH1)") (class "Default")
      (node (ref "U900") (pin "H1") (pinfunction "PX04_H1") (pintype "bidirectional+no_connect"))
    )
    (net (code "103") (name "unconnected-(U900-PX05-PadG1)") (class "Default")
      (node (ref "U900") (pin "G1") (pinfunction "PX05_G1") (pintype "bidirectional+no_connect"))
    )
    (net (code "104") (name "unconnected-(U900-PX06-PadF3)") (class "Default")
      (node (ref "U900") (pin "F3") (pinfunction "PX06_F3") (pintype "bidirectional+no_connect"))
    )
    (net (code "105") (name "unconnected-(U900-PX07-PadF4)") (class "Default")
      (node (ref "U900") (pin "F4") (pinfunction "PX07_F4") (pintype "bidirectional+no_connect"))
    )
    (net (code "106") (name "unconnected-(U900-PX08-PadE3)") (class "Default")
      (node (ref "U900") (pin "E3") (pinfunction "PX08_E3") (pintype "bidirectional+no_connect"))
    )
    (net (code "107") (name "unconnected-(U900-PX09-PadE4)") (class "Default")
      (node (ref "U900") (pin "E4") (pinfunction "PX09_E4") (pintype "bidirectional+no_connect"))
    )
    (net (code "108") (name "unconnected-(U900-PX10-PadD2)") (class "Default")
      (node (ref "U900") (pin "D2") (pinfunction "PX10_D2") (pintype "bidirectional+no_connect"))
    )
    (net (code "109") (name "unconnected-(U900-PX12-PadD1)") (class "Default")
      (node (ref "U900") (pin "D1") (pinfunction "PX12_D1") (pintype "bidirectional+no_connect"))
    )
    (net (code "110") (name "unconnected-(U900-PX16_{slash}_PX53-PadD4)") (class "Default")
      (node (ref "U900") (pin "D4") (pinfunction "PX16_/_PX53_D4") (pintype "bidirectional+no_connect"))
    )
    (net (code "111") (name "unconnected-(U900-PX23-PadK1)") (class "Default")
      (node (ref "U900") (pin "K1") (pinfunction "PX23_K1") (pintype "bidirectional+no_connect"))
    )
    (net (code "112") (name "unconnected-(U900-PX24-PadJ2)") (class "Default")
      (node (ref "U900") (pin "J2") (pinfunction "PX24_J2") (pintype "bidirectional+no_connect"))
    )
    (net (code "113") (name "unconnected-(U900-PX25-PadH4)") (class "Default")
      (node (ref "U900") (pin "H4") (pinfunction "PX25_H4") (pintype "bidirectional+no_connect"))
    )
    (net (code "114") (name "unconnected-(U900-PX26-PadJ3)") (class "Default")
      (node (ref "U900") (pin "J3") (pinfunction "PX26_J3") (pintype "bidirectional+no_connect"))
    )
    (net (code "115") (name "unconnected-(U900-PX31-PadH5)") (class "Default")
      (node (ref "U900") (pin "H5") (pinfunction "PX31_H5") (pintype "bidirectional+no_connect"))
    )
  )
)
